# HURCBiomechSockSchematic.net
KiCad netlist of a schematic drawn in EAGLE
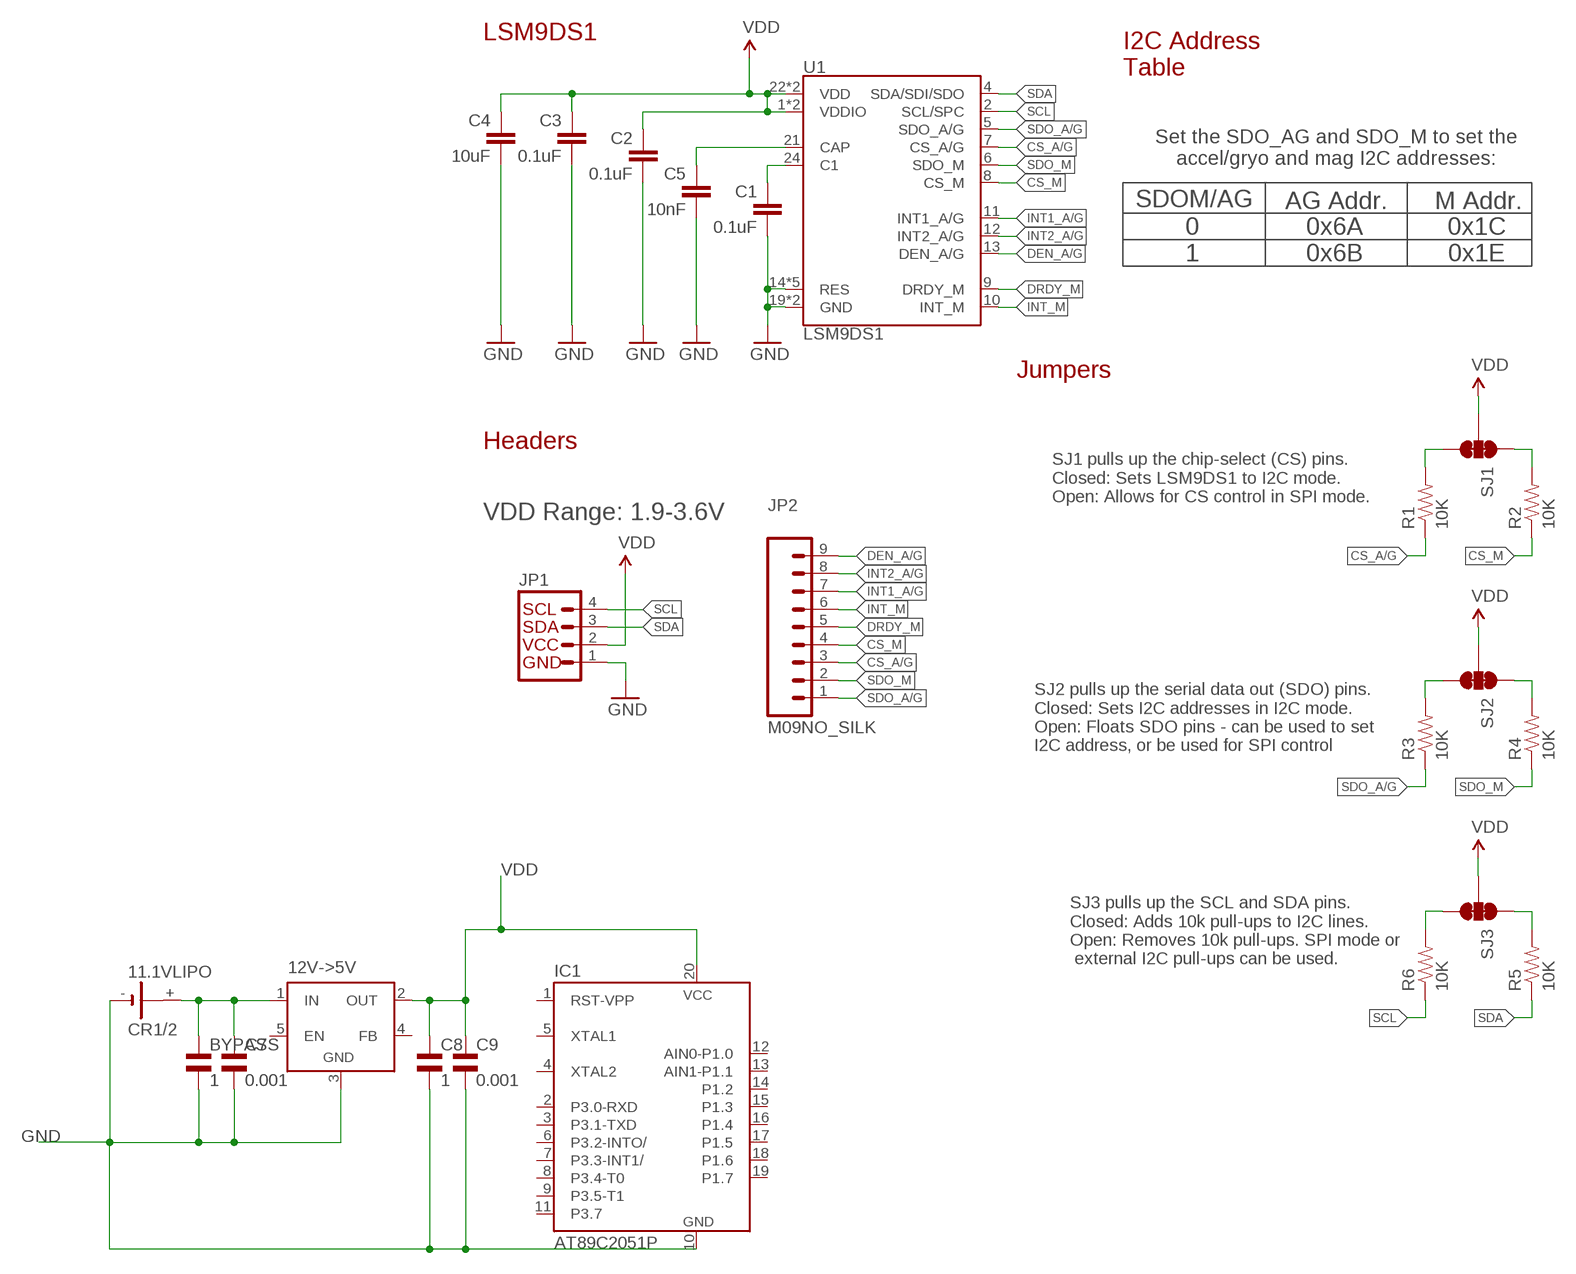
[diagram p0: schematic, sheet 1]

(export (version "E")
  (design (tool "Eeschema 10.0.6"))
  (components
    (comp (ref "11.1VLIPO")
      (value "CR1/2")
      (footprint "eagle-import:CR1_2")
      (libsource (lib "eagle-import") (part "CR1/2"))
    )
    (comp (ref "12V->5V")
      (value "LM2596TV")
      (footprint "eagle-import:TO220-51")
      (libsource (lib "eagle-import") (part "LM2596TV"))
    )
    (comp (ref "BYPASS")
      (value "1")
      (footprint "eagle-import:EU25-10")
      (libsource (lib "eagle-import") (part "EL-BI25-10AXIAL"))
    )
    (comp (ref "C1")
      (value "0.1uF")
      (footprint "eagle-import:0603-CAP")
      (libsource (lib "eagle-import") (part "0.1UF-25V(+80/-20%)(0603)"))
    )
    (comp (ref "C2")
      (value "0.1uF")
      (footprint "eagle-import:0603-CAP")
      (libsource (lib "eagle-import") (part "0.1UF-25V(+80/-20%)(0603)"))
    )
    (comp (ref "C3")
      (value "0.1uF")
      (footprint "eagle-import:0603-CAP")
      (libsource (lib "eagle-import") (part "0.1UF-25V(+80/-20%)(0603)"))
    )
    (comp (ref "C4")
      (value "10uF")
      (footprint "eagle-import:0603-CAP")
      (libsource (lib "eagle-import") (part "10UF-6.3V-20%(0603)"))
    )
    (comp (ref "C5")
      (value "10nF")
      (footprint "eagle-import:0603-CAP")
      (libsource (lib "eagle-import") (part "10NF/10000PF-50V-10%(0603)"))
    )
    (comp (ref "C7")
      (value "0.001")
      (footprint "eagle-import:EU25-10")
      (libsource (lib "eagle-import") (part "EL-BI25-10AXIAL"))
    )
    (comp (ref "C8")
      (value "1")
      (footprint "eagle-import:EU25-10")
      (libsource (lib "eagle-import") (part "EL-BI25-10AXIAL"))
    )
    (comp (ref "C9")
      (value "0.001")
      (footprint "eagle-import:EU25-10")
      (libsource (lib "eagle-import") (part "EL-BI25-10AXIAL"))
    )
    (comp (ref "IC1")
      (value "AT89C2051P")
      (footprint "eagle-import:DIL20")
      (fields (field (name "MPN") "AT89C2051-12PU"))
      (libsource (lib "eagle-import") (part "AT89C2051P"))
    )
    (comp (ref "JP1")
      (value "I2C_STANDARD_NO_SILK")
      (footprint "eagle-import:1X04_NO_SILK")
      (libsource (lib "eagle-import") (part "I2C_STANDARD_NO_SILK"))
    )
    (comp (ref "JP2")
      (value "M09NO_SILK")
      (footprint "eagle-import:1X09_NO_SILK")
      (libsource (lib "eagle-import") (part "M09NO_SILK"))
    )
    (comp (ref "R1")
      (value "10K")
      (footprint "eagle-import:0603-RES")
      (libsource (lib "eagle-import") (part "10KOHM-1/10W-1%(0603)0603"))
    )
    (comp (ref "R2")
      (value "10K")
      (footprint "eagle-import:0603-RES")
      (libsource (lib "eagle-import") (part "10KOHM-1/10W-1%(0603)0603"))
    )
    (comp (ref "R3")
      (value "10K")
      (footprint "eagle-import:0603-RES")
      (libsource (lib "eagle-import") (part "10KOHM-1/10W-1%(0603)0603"))
    )
    (comp (ref "R4")
      (value "10K")
      (footprint "eagle-import:0603-RES")
      (libsource (lib "eagle-import") (part "10KOHM-1/10W-1%(0603)0603"))
    )
    (comp (ref "R5")
      (value "10K")
      (footprint "eagle-import:0603-RES")
      (libsource (lib "eagle-import") (part "10KOHM-1/10W-1%(0603)0603"))
    )
    (comp (ref "R6")
      (value "10K")
      (footprint "eagle-import:0603-RES")
      (libsource (lib "eagle-import") (part "10KOHM-1/10W-1%(0603)0603"))
    )
    (comp (ref "SJ1")
      (value "JUMPER-PAD-3-NC_BY_TRACE")
      (footprint "eagle-import:PAD-JUMPER-3-3OF3_NC_BY_TRACE_YES_SILK_FULL_BOX")
      (libsource (lib "eagle-import") (part "JUMPER-PAD-3-NC_BY_TRACE"))
    )
    (comp (ref "SJ2")
      (value "JUMPER-PAD-3-NC_BY_TRACE")
      (footprint "eagle-import:PAD-JUMPER-3-3OF3_NC_BY_TRACE_YES_SILK_FULL_BOX")
      (libsource (lib "eagle-import") (part "JUMPER-PAD-3-NC_BY_TRACE"))
    )
    (comp (ref "SJ3")
      (value "JUMPER-PAD-3-NC_BY_TRACE")
      (footprint "eagle-import:PAD-JUMPER-3-3OF3_NC_BY_TRACE_YES_SILK_FULL_BOX")
      (libsource (lib "eagle-import") (part "JUMPER-PAD-3-NC_BY_TRACE"))
    )
    (comp (ref "U1")
      (value "LSM9DS1")
      (footprint "eagle-import:LGA24-8X4")
      (libsource (lib "eagle-import") (part "LSM9DS1"))
    )
  )
  (nets
    (net (code "1") (name "CS_A{slash}G") (class "Default")
      (node (ref "JP2") (pin "3") (pinfunction "3_3") (pintype "passive"))
      (node (ref "R1") (pin "1") (pinfunction "1_1") (pintype "passive"))
      (node (ref "U1") (pin "7") (pinfunction "CS_A/G_7") (pintype "bidirectional"))
    )
    (net (code "2") (name "CS_M") (class "Default")
      (node (ref "JP2") (pin "4") (pinfunction "4_4") (pintype "passive"))
      (node (ref "R2") (pin "1") (pinfunction "1_1") (pintype "passive"))
      (node (ref "U1") (pin "8") (pinfunction "CS_M_8") (pintype "bidirectional"))
    )
    (net (code "3") (name "DEN_A{slash}G") (class "Default")
      (node (ref "JP2") (pin "9") (pinfunction "9_9") (pintype "passive"))
      (node (ref "U1") (pin "13") (pinfunction "DEN_A/G_13") (pintype "bidirectional"))
    )
    (net (code "4") (name "DRDY_M") (class "Default")
      (node (ref "JP2") (pin "5") (pinfunction "5_5") (pintype "passive"))
      (node (ref "U1") (pin "9") (pinfunction "DRDY_M_9") (pintype "bidirectional"))
    )
    (net (code "5") (name "GND") (class "Default")
      (node (ref "11.1VLIPO") (pin "-") (pinfunction "-_-") (pintype "passive"))
      (node (ref "12V->5V") (pin "3") (pinfunction "GND_3") (pintype "power_in"))
      (node (ref "BYPASS") (pin "2") (pinfunction "2_2") (pintype "passive"))
      (node (ref "C1") (pin "2") (pinfunction "2_2") (pintype "passive"))
      (node (ref "C2") (pin "2") (pinfunction "2_2") (pintype "passive"))
      (node (ref "C3") (pin "2") (pinfunction "2_2") (pintype "passive"))
      (node (ref "C4") (pin "2") (pinfunction "2_2") (pintype "passive"))
      (node (ref "C5") (pin "2") (pinfunction "2_2") (pintype "passive"))
      (node (ref "C7") (pin "2") (pinfunction "2_2") (pintype "passive"))
      (node (ref "C8") (pin "2") (pinfunction "2_2") (pintype "passive"))
      (node (ref "C9") (pin "2") (pinfunction "2_2") (pintype "passive"))
      (node (ref "IC1") (pin "10") (pinfunction "GND_10") (pintype "power_in"))
      (node (ref "JP1") (pin "1") (pinfunction "1_1") (pintype "passive"))
      (node (ref "U1") (pin "14") (pinfunction "RES_14") (pintype "bidirectional"))
      (node (ref "U1") (pin "15") (pinfunction "RES_15") (pintype "bidirectional"))
      (node (ref "U1") (pin "16") (pinfunction "RES_16") (pintype "bidirectional"))
      (node (ref "U1") (pin "17") (pinfunction "RES_17") (pintype "bidirectional"))
      (node (ref "U1") (pin "18") (pinfunction "RES_18") (pintype "bidirectional"))
      (node (ref "U1") (pin "19") (pinfunction "GND_19") (pintype "bidirectional"))
      (node (ref "U1") (pin "20") (pinfunction "GND_20") (pintype "bidirectional"))
    )
    (net (code "6") (name "INT1_A{slash}G") (class "Default")
      (node (ref "JP2") (pin "7") (pinfunction "7_7") (pintype "passive"))
      (node (ref "U1") (pin "11") (pinfunction "INT1_A/G_11") (pintype "bidirectional"))
    )
    (net (code "7") (name "INT2_A{slash}G") (class "Default")
      (node (ref "JP2") (pin "8") (pinfunction "8_8") (pintype "passive"))
      (node (ref "U1") (pin "12") (pinfunction "INT2_A/G_12") (pintype "bidirectional"))
    )
    (net (code "8") (name "INT_M") (class "Default")
      (node (ref "JP2") (pin "6") (pinfunction "6_6") (pintype "passive"))
      (node (ref "U1") (pin "10") (pinfunction "INT_M_10") (pintype "bidirectional"))
    )
    (net (code "9") (name "Net-(12V->5V-IN)") (class "Default")
      (node (ref "11.1VLIPO") (pin "+") (pinfunction "+_+") (pintype "passive"))
      (node (ref "12V->5V") (pin "1") (pinfunction "IN_1") (pintype "input"))
      (node (ref "BYPASS") (pin "1") (pinfunction "1_1") (pintype "passive"))
      (node (ref "C7") (pin "1") (pinfunction "1_1") (pintype "passive"))
    )
    (net (code "10") (name "Net-(R1-Pad2)") (class "Default")
      (node (ref "R1") (pin "2") (pinfunction "2_2") (pintype "passive"))
      (node (ref "SJ1") (pin "3") (pinfunction "3_3") (pintype "passive"))
    )
    (net (code "11") (name "Net-(R2-Pad2)") (class "Default")
      (node (ref "R2") (pin "2") (pinfunction "2_2") (pintype "passive"))
      (node (ref "SJ1") (pin "1") (pinfunction "1_1") (pintype "passive"))
    )
    (net (code "12") (name "Net-(R3-Pad2)") (class "Default")
      (node (ref "R3") (pin "2") (pinfunction "2_2") (pintype "passive"))
      (node (ref "SJ2") (pin "3") (pinfunction "3_3") (pintype "passive"))
    )
    (net (code "13") (name "Net-(R4-Pad2)") (class "Default")
      (node (ref "R4") (pin "2") (pinfunction "2_2") (pintype "passive"))
      (node (ref "SJ2") (pin "1") (pinfunction "1_1") (pintype "passive"))
    )
    (net (code "14") (name "Net-(R5-Pad2)") (class "Default")
      (node (ref "R5") (pin "2") (pinfunction "2_2") (pintype "passive"))
      (node (ref "SJ3") (pin "1") (pinfunction "1_1") (pintype "passive"))
    )
    (net (code "15") (name "Net-(R6-Pad2)") (class "Default")
      (node (ref "R6") (pin "2") (pinfunction "2_2") (pintype "passive"))
      (node (ref "SJ3") (pin "3") (pinfunction "3_3") (pintype "passive"))
    )
    (net (code "16") (name "Net-(U1-C1)") (class "Default")
      (node (ref "C1") (pin "1") (pinfunction "1_1") (pintype "passive"))
      (node (ref "U1") (pin "24") (pinfunction "C1_24") (pintype "bidirectional"))
    )
    (net (code "17") (name "Net-(U1-CAP)") (class "Default")
      (node (ref "C5") (pin "1") (pinfunction "1_1") (pintype "passive"))
      (node (ref "U1") (pin "21") (pinfunction "CAP_21") (pintype "bidirectional"))
    )
    (net (code "18") (name "SCL") (class "Default")
      (node (ref "JP1") (pin "4") (pinfunction "4_4") (pintype "passive"))
      (node (ref "R6") (pin "1") (pinfunction "1_1") (pintype "passive"))
      (node (ref "U1") (pin "2") (pinfunction "SCL/SPC_2") (pintype "bidirectional"))
    )
    (net (code "19") (name "SDA") (class "Default")
      (node (ref "JP1") (pin "3") (pinfunction "3_3") (pintype "passive"))
      (node (ref "R5") (pin "1") (pinfunction "1_1") (pintype "passive"))
      (node (ref "U1") (pin "4") (pinfunction "SDA/SDI/SDO_4") (pintype "bidirectional"))
    )
    (net (code "20") (name "SDO_A{slash}G") (class "Default")
      (node (ref "JP2") (pin "1") (pinfunction "1_1") (pintype "passive"))
      (node (ref "R3") (pin "1") (pinfunction "1_1") (pintype "passive"))
      (node (ref "U1") (pin "5") (pinfunction "SDO_A/G_5") (pintype "bidirectional"))
    )
    (net (code "21") (name "SDO_M") (class "Default")
      (node (ref "JP2") (pin "2") (pinfunction "2_2") (pintype "passive"))
      (node (ref "R4") (pin "1") (pinfunction "1_1") (pintype "passive"))
      (node (ref "U1") (pin "6") (pinfunction "SDO_M_6") (pintype "bidirectional"))
    )
    (net (code "22") (name "VDD") (class "Default")
      (node (ref "12V->5V") (pin "2") (pinfunction "OUT_2") (pintype "output"))
      (node (ref "C2") (pin "1") (pinfunction "1_1") (pintype "passive"))
      (node (ref "C3") (pin "1") (pinfunction "1_1") (pintype "passive"))
      (node (ref "C4") (pin "1") (pinfunction "1_1") (pintype "passive"))
      (node (ref "C8") (pin "1") (pinfunction "1_1") (pintype "passive"))
      (node (ref "C9") (pin "1") (pinfunction "1_1") (pintype "passive"))
      (node (ref "IC1") (pin "20") (pinfunction "VCC_20") (pintype "power_in"))
      (node (ref "JP1") (pin "2") (pinfunction "2_2") (pintype "passive"))
      (node (ref "SJ1") (pin "2") (pinfunction "2_2") (pintype "passive"))
      (node (ref "SJ2") (pin "2") (pinfunction "2_2") (pintype "passive"))
      (node (ref "SJ3") (pin "2") (pinfunction "2_2") (pintype "passive"))
      (node (ref "U1") (pin "1") (pinfunction "VDDIO_1") (pintype "bidirectional"))
      (node (ref "U1") (pin "22") (pinfunction "VDD_22") (pintype "bidirectional"))
      (node (ref "U1") (pin "23") (pinfunction "VDD_23") (pintype "bidirectional"))
      (node (ref "U1") (pin "3") (pinfunction "VDDIO_3") (pintype "bidirectional"))
    )
    (net (code "23") (name "unconnected-(11.1VLIPO-+-Pad+@1)") (class "Default")
      (node (ref "11.1VLIPO") (pin "+@1") (pinfunction "+_+@1") (pintype "passive"))
    )
    (net (code "24") (name "unconnected-(12V->5V-EN-Pad5)") (class "Default")
      (node (ref "12V->5V") (pin "5") (pinfunction "EN_5") (pintype "input"))
    )
    (net (code "25") (name "unconnected-(12V->5V-FB-Pad4)") (class "Default")
      (node (ref "12V->5V") (pin "4") (pinfunction "FB_4") (pintype "input"))
    )
    (net (code "26") (name "unconnected-(IC1-AIN0-P1.0-Pad12)") (class "Default")
      (node (ref "IC1") (pin "12") (pinfunction "AIN0-P1.0_12") (pintype "bidirectional"))
    )
    (net (code "27") (name "unconnected-(IC1-AIN1-P1.1-Pad13)") (class "Default")
      (node (ref "IC1") (pin "13") (pinfunction "AIN1-P1.1_13") (pintype "bidirectional"))
    )
    (net (code "28") (name "unconnected-(IC1-P1.2-Pad14)") (class "Default")
      (node (ref "IC1") (pin "14") (pinfunction "P1.2_14") (pintype "bidirectional"))
    )
    (net (code "29") (name "unconnected-(IC1-P1.3-Pad15)") (class "Default")
      (node (ref "IC1") (pin "15") (pinfunction "P1.3_15") (pintype "bidirectional"))
    )
    (net (code "30") (name "unconnected-(IC1-P1.4-Pad16)") (class "Default")
      (node (ref "IC1") (pin "16") (pinfunction "P1.4_16") (pintype "bidirectional"))
    )
    (net (code "31") (name "unconnected-(IC1-P1.5-Pad17)") (class "Default")
      (node (ref "IC1") (pin "17") (pinfunction "P1.5_17") (pintype "bidirectional"))
    )
    (net (code "32") (name "unconnected-(IC1-P1.6-Pad18)") (class "Default")
      (node (ref "IC1") (pin "18") (pinfunction "P1.6_18") (pintype "bidirectional"))
    )
    (net (code "33") (name "unconnected-(IC1-P1.7-Pad19)") (class "Default")
      (node (ref "IC1") (pin "19") (pinfunction "P1.7_19") (pintype "bidirectional"))
    )
    (net (code "34") (name "unconnected-(IC1-P3.0-RXD-Pad2)") (class "Default")
      (node (ref "IC1") (pin "2") (pinfunction "P3.0-RXD_2") (pintype "bidirectional"))
    )
    (net (code "35") (name "unconnected-(IC1-P3.1-TXD-Pad3)") (class "Default")
      (node (ref "IC1") (pin "3") (pinfunction "P3.1-TXD_3") (pintype "bidirectional"))
    )
    (net (code "36") (name "unconnected-(IC1-P3.2-INTO{slash}-Pad6)") (class "Default")
      (node (ref "IC1") (pin "6") (pinfunction "P3.2-INTO/_6") (pintype "bidirectional"))
    )
    (net (code "37") (name "unconnected-(IC1-P3.3-INT1{slash}-Pad7)") (class "Default")
      (node (ref "IC1") (pin "7") (pinfunction "P3.3-INT1/_7") (pintype "bidirectional"))
    )
    (net (code "38") (name "unconnected-(IC1-P3.4-T0-Pad8)") (class "Default")
      (node (ref "IC1") (pin "8") (pinfunction "P3.4-T0_8") (pintype "bidirectional"))
    )
    (net (code "39") (name "unconnected-(IC1-P3.5-T1-Pad9)") (class "Default")
      (node (ref "IC1") (pin "9") (pinfunction "P3.5-T1_9") (pintype "bidirectional"))
    )
    (net (code "40") (name "unconnected-(IC1-P3.7-Pad11)") (class "Default")
      (node (ref "IC1") (pin "11") (pinfunction "P3.7_11") (pintype "bidirectional"))
    )
    (net (code "41") (name "unconnected-(IC1-RST-VPP-Pad1)") (class "Default")
      (node (ref "IC1") (pin "1") (pinfunction "RST-VPP_1") (pintype "input"))
    )
    (net (code "42") (name "unconnected-(IC1-XTAL1-Pad5)") (class "Default")
      (node (ref "IC1") (pin "5") (pinfunction "XTAL1_5") (pintype "input"))
    )
    (net (code "43") (name "unconnected-(IC1-XTAL2-Pad4)") (class "Default")
      (node (ref "IC1") (pin "4") (pinfunction "XTAL2_4") (pintype "output"))
    )
  )
)
